# encoder.net
KiCad netlist of a schematic drawn in EAGLE
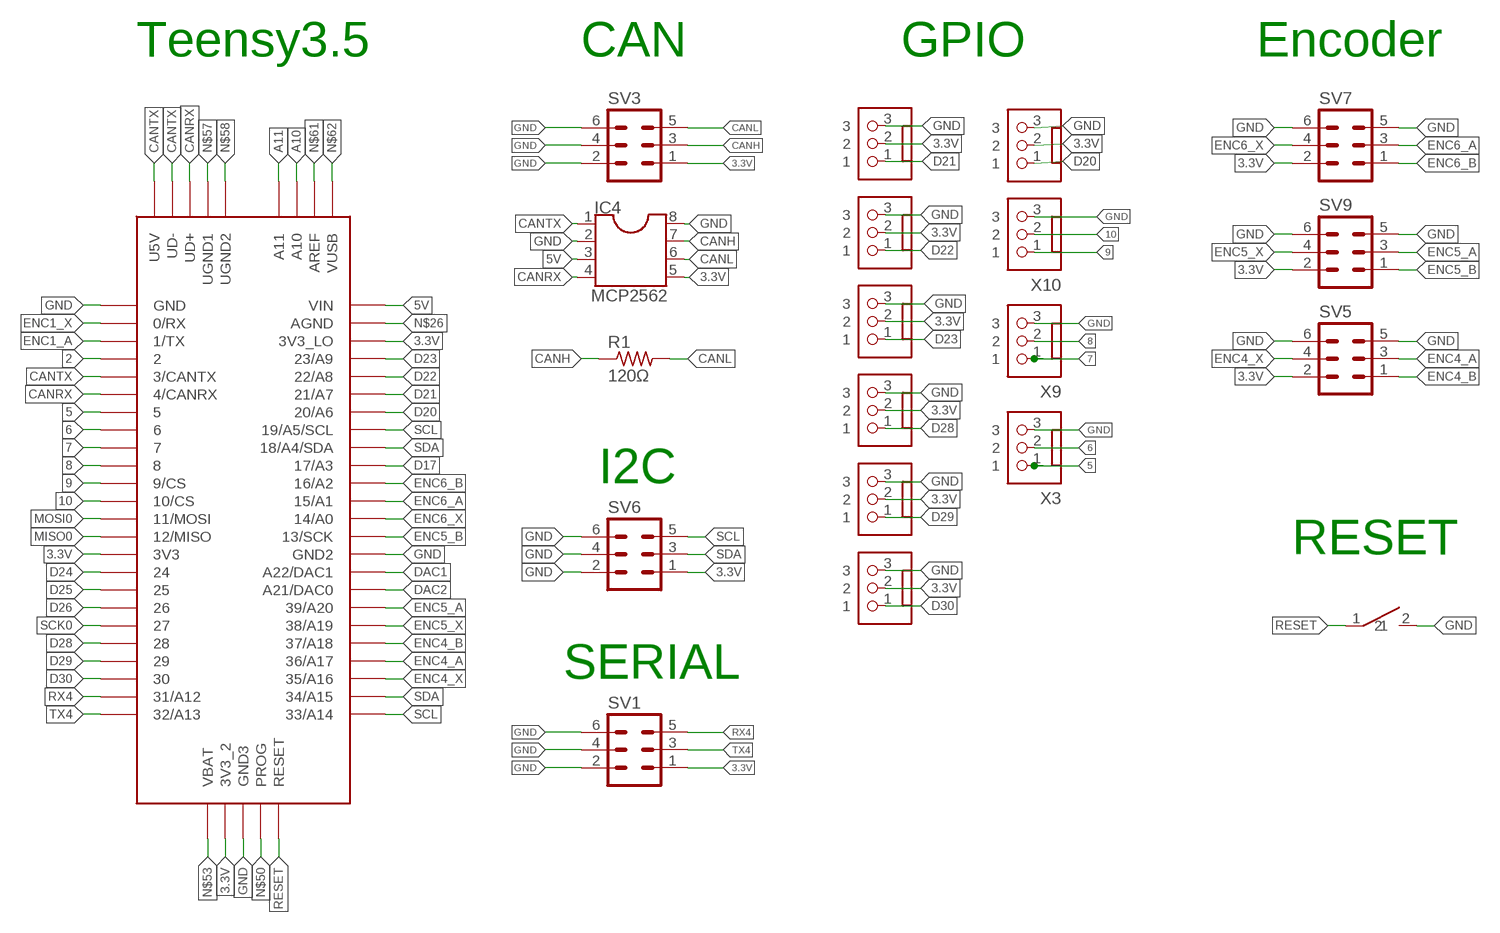
[diagram p0: schematic, sheet 1]

(export (version "E")
  (design (tool "Eeschema 10.0.6"))
  (components
    (comp (ref "IC4")
      (value "MCP2562")
      (footprint "eagle-import:DIL08")
      (libsource (lib "eagle-import") (part "DIL8"))
    )
    (comp (ref "R1")
      (value "120Ω")
      (footprint "eagle-import:0207_7")
      (libsource (lib "eagle-import") (part "R-US_0207/7"))
    )
    (comp (ref "SV1")
      (value "ML6")
      (footprint "eagle-import:ML6")
      (libsource (lib "eagle-import") (part "ML6"))
    )
    (comp (ref "SV3")
      (value "ML6")
      (footprint "eagle-import:ML6")
      (libsource (lib "eagle-import") (part "ML6"))
    )
    (comp (ref "SV5")
      (value "ML6")
      (footprint "eagle-import:ML6")
      (libsource (lib "eagle-import") (part "ML6"))
    )
    (comp (ref "SV6")
      (value "ML6")
      (footprint "eagle-import:ML6")
      (libsource (lib "eagle-import") (part "ML6"))
    )
    (comp (ref "SV7")
      (value "ML6")
      (footprint "eagle-import:ML6")
      (libsource (lib "eagle-import") (part "ML6"))
    )
    (comp (ref "SV9")
      (value "ML6")
      (footprint "eagle-import:ML6")
      (libsource (lib "eagle-import") (part "ML6"))
    )
    (comp (ref "TACT_SWITCH1")
      (value "TACT_SWITCH")
      (footprint "eagle-import:TACT_SWITCH")
      (libsource (lib "eagle-import") (part "TACT_SWITCH"))
    )
    (comp (ref "U$1")
      (value "TEENSY_3.5/3.6")
      (footprint "eagle-import:TEENSY_3.5_3.6")
      (libsource (lib "eagle-import") (part "TEENSY_3.5/3.6"))
    )
    (comp (ref "X3")
      (value "JST-XH-03-PIN-LONG-PAD")
      (footprint "eagle-import:JST-XH-03-PACKAGE-LONG-PAD")
      (libsource (lib "eagle-import") (part "JST-XH-03-PIN-LONG-PAD"))
    )
    (comp (ref "X6")
      (value "JST-XH-03-PIN-LONG-PAD")
      (footprint "eagle-import:JST-XH-03-PACKAGE-LONG-PAD")
      (libsource (lib "eagle-import") (part "JST-XH-03-PIN-LONG-PAD"))
    )
    (comp (ref "X7")
      (value "JST-XH-03-PIN-LONG-PAD")
      (footprint "eagle-import:JST-XH-03-PACKAGE-LONG-PAD")
      (libsource (lib "eagle-import") (part "JST-XH-03-PIN-LONG-PAD"))
    )
    (comp (ref "X8")
      (value "JST-XH-03-PIN-LONG-PAD")
      (footprint "eagle-import:JST-XH-03-PACKAGE-LONG-PAD")
      (libsource (lib "eagle-import") (part "JST-XH-03-PIN-LONG-PAD"))
    )
    (comp (ref "X9")
      (value "JST-XH-03-PIN-LONG-PAD")
      (footprint "eagle-import:JST-XH-03-PACKAGE-LONG-PAD")
      (libsource (lib "eagle-import") (part "JST-XH-03-PIN-LONG-PAD"))
    )
    (comp (ref "X10")
      (value "JST-XH-03-PIN-LONG-PAD")
      (footprint "eagle-import:JST-XH-03-PACKAGE-LONG-PAD")
      (libsource (lib "eagle-import") (part "JST-XH-03-PIN-LONG-PAD"))
    )
    (comp (ref "X12")
      (value "JST-XH-03-PIN-LONG-PAD")
      (footprint "eagle-import:JST-XH-03-PACKAGE-LONG-PAD")
      (libsource (lib "eagle-import") (part "JST-XH-03-PIN-LONG-PAD"))
    )
    (comp (ref "X13")
      (value "JST-XH-03-PIN-LONG-PAD")
      (footprint "eagle-import:JST-XH-03-PACKAGE-LONG-PAD")
      (libsource (lib "eagle-import") (part "JST-XH-03-PIN-LONG-PAD"))
    )
    (comp (ref "X14")
      (value "JST-XH-03-PIN-LONG-PAD")
      (footprint "eagle-import:JST-XH-03-PACKAGE-LONG-PAD")
      (libsource (lib "eagle-import") (part "JST-XH-03-PIN-LONG-PAD"))
    )
    (comp (ref "X15")
      (value "JST-XH-03-PIN-LONG-PAD")
      (footprint "eagle-import:JST-XH-03-PACKAGE-LONG-PAD")
      (libsource (lib "eagle-import") (part "JST-XH-03-PIN-LONG-PAD"))
    )
  )
  (nets
    (net (code "1") (name "2") (class "Default")
      (node (ref "U$1") (pin "2") (pinfunction "2_2") (pintype "bidirectional"))
    )
    (net (code "2") (name "3.3V") (class "Default")
      (node (ref "IC4") (pin "5") (pinfunction "5_5") (pintype "passive"))
      (node (ref "SV1") (pin "1") (pinfunction "1_1") (pintype "passive"))
      (node (ref "SV3") (pin "1") (pinfunction "1_1") (pintype "passive"))
      (node (ref "SV5") (pin "2") (pinfunction "2_2") (pintype "passive"))
      (node (ref "SV6") (pin "1") (pinfunction "1_1") (pintype "passive"))
      (node (ref "SV7") (pin "2") (pinfunction "2_2") (pintype "passive"))
      (node (ref "SV9") (pin "2") (pinfunction "2_2") (pintype "passive"))
      (node (ref "U$1") (pin "3V3") (pinfunction "3V3_3V3") (pintype "bidirectional"))
      (node (ref "U$1") (pin "3V3_2") (pinfunction "3V3_2_3V3_2") (pintype "bidirectional"))
      (node (ref "U$1") (pin "3V3_LO") (pinfunction "3V3_LO_3V3_LO") (pintype "bidirectional"))
      (node (ref "X12") (pin "2") (pinfunction "2_2") (pintype "bidirectional"))
      (node (ref "X13") (pin "2") (pinfunction "2_2") (pintype "bidirectional"))
      (node (ref "X14") (pin "2") (pinfunction "2_2") (pintype "bidirectional"))
      (node (ref "X15") (pin "2") (pinfunction "2_2") (pintype "bidirectional"))
      (node (ref "X6") (pin "2") (pinfunction "2_2") (pintype "bidirectional"))
      (node (ref "X7") (pin "2") (pinfunction "2_2") (pintype "bidirectional"))
      (node (ref "X8") (pin "2") (pinfunction "2_2") (pintype "bidirectional"))
    )
    (net (code "3") (name "5") (class "Default")
      (node (ref "U$1") (pin "5") (pinfunction "5_5") (pintype "bidirectional"))
      (node (ref "X3") (pin "1") (pinfunction "1_1") (pintype "bidirectional"))
    )
    (net (code "4") (name "5V") (class "Default")
      (node (ref "IC4") (pin "3") (pinfunction "3_3") (pintype "passive"))
      (node (ref "U$1") (pin "VIN") (pinfunction "VIN_VIN") (pintype "bidirectional"))
    )
    (net (code "5") (name "6") (class "Default")
      (node (ref "U$1") (pin "6") (pinfunction "6_6") (pintype "bidirectional"))
      (node (ref "X3") (pin "2") (pinfunction "2_2") (pintype "bidirectional"))
    )
    (net (code "6") (name "7") (class "Default")
      (node (ref "U$1") (pin "7") (pinfunction "7_7") (pintype "bidirectional"))
      (node (ref "X9") (pin "1") (pinfunction "1_1") (pintype "bidirectional"))
    )
    (net (code "7") (name "8") (class "Default")
      (node (ref "U$1") (pin "8") (pinfunction "8_8") (pintype "bidirectional"))
      (node (ref "X9") (pin "2") (pinfunction "2_2") (pintype "bidirectional"))
    )
    (net (code "8") (name "9") (class "Default")
      (node (ref "U$1") (pin "9/CS") (pinfunction "9/CS_9/CS") (pintype "bidirectional"))
      (node (ref "X10") (pin "1") (pinfunction "1_1") (pintype "bidirectional"))
    )
    (net (code "9") (name "10") (class "Default")
      (node (ref "U$1") (pin "10/CS") (pinfunction "10/CS_10/CS") (pintype "bidirectional"))
      (node (ref "X10") (pin "2") (pinfunction "2_2") (pintype "bidirectional"))
    )
    (net (code "10") (name "A10") (class "Default")
      (node (ref "U$1") (pin "A10") (pinfunction "A10_A10") (pintype "bidirectional"))
    )
    (net (code "11") (name "A11") (class "Default")
      (node (ref "U$1") (pin "A11") (pinfunction "A11_A11") (pintype "bidirectional"))
    )
    (net (code "12") (name "CANH") (class "Default")
      (node (ref "IC4") (pin "7") (pinfunction "7_7") (pintype "passive"))
      (node (ref "R1") (pin "1") (pinfunction "1_1") (pintype "passive"))
      (node (ref "SV3") (pin "3") (pinfunction "3_3") (pintype "passive"))
    )
    (net (code "13") (name "CANL") (class "Default")
      (node (ref "IC4") (pin "6") (pinfunction "6_6") (pintype "passive"))
      (node (ref "R1") (pin "2") (pinfunction "2_2") (pintype "passive"))
      (node (ref "SV3") (pin "5") (pinfunction "5_5") (pintype "passive"))
    )
    (net (code "14") (name "CANRX") (class "Default")
      (node (ref "IC4") (pin "4") (pinfunction "4_4") (pintype "passive"))
      (node (ref "U$1") (pin "4/CANRX") (pinfunction "4/CANRX_4/CANRX") (pintype "bidirectional"))
      (node (ref "U$1") (pin "UD+") (pinfunction "UD+_UD+") (pintype "bidirectional"))
    )
    (net (code "15") (name "CANTX") (class "Default")
      (node (ref "IC4") (pin "1") (pinfunction "1_1") (pintype "passive"))
      (node (ref "U$1") (pin "3/CANTX") (pinfunction "3/CANTX_3/CANTX") (pintype "bidirectional"))
      (node (ref "U$1") (pin "U5V") (pinfunction "U5V_U5V") (pintype "bidirectional"))
      (node (ref "U$1") (pin "UD-") (pinfunction "UD-_UD-") (pintype "bidirectional"))
    )
    (net (code "16") (name "D17") (class "Default")
      (node (ref "U$1") (pin "17/A3") (pinfunction "17/A3_17/A3") (pintype "bidirectional"))
    )
    (net (code "17") (name "D20") (class "Default")
      (node (ref "U$1") (pin "20/A6") (pinfunction "20/A6_20/A6") (pintype "bidirectional"))
      (node (ref "X6") (pin "1") (pinfunction "1_1") (pintype "bidirectional"))
    )
    (net (code "18") (name "D21") (class "Default")
      (node (ref "U$1") (pin "21/A7") (pinfunction "21/A7_21/A7") (pintype "bidirectional"))
      (node (ref "X7") (pin "1") (pinfunction "1_1") (pintype "bidirectional"))
    )
    (net (code "19") (name "D22") (class "Default")
      (node (ref "U$1") (pin "22/A8") (pinfunction "22/A8_22/A8") (pintype "bidirectional"))
      (node (ref "X12") (pin "1") (pinfunction "1_1") (pintype "bidirectional"))
    )
    (net (code "20") (name "D23") (class "Default")
      (node (ref "U$1") (pin "23/A9") (pinfunction "23/A9_23/A9") (pintype "bidirectional"))
      (node (ref "X13") (pin "1") (pinfunction "1_1") (pintype "bidirectional"))
    )
    (net (code "21") (name "D24") (class "Default")
      (node (ref "U$1") (pin "24") (pinfunction "24_24") (pintype "bidirectional"))
    )
    (net (code "22") (name "D25") (class "Default")
      (node (ref "U$1") (pin "25") (pinfunction "25_25") (pintype "bidirectional"))
    )
    (net (code "23") (name "D26") (class "Default")
      (node (ref "U$1") (pin "26") (pinfunction "26_26") (pintype "bidirectional"))
    )
    (net (code "24") (name "D28") (class "Default")
      (node (ref "U$1") (pin "28") (pinfunction "28_28") (pintype "bidirectional"))
      (node (ref "X8") (pin "1") (pinfunction "1_1") (pintype "bidirectional"))
    )
    (net (code "25") (name "D29") (class "Default")
      (node (ref "U$1") (pin "29") (pinfunction "29_29") (pintype "bidirectional"))
      (node (ref "X14") (pin "1") (pinfunction "1_1") (pintype "bidirectional"))
    )
    (net (code "26") (name "D30") (class "Default")
      (node (ref "U$1") (pin "30") (pinfunction "30_30") (pintype "bidirectional"))
      (node (ref "X15") (pin "1") (pinfunction "1_1") (pintype "bidirectional"))
    )
    (net (code "27") (name "DAC1") (class "Default")
      (node (ref "U$1") (pin "A22/DAC1") (pinfunction "A22/DAC1_A22/DAC1") (pintype "bidirectional"))
    )
    (net (code "28") (name "DAC2") (class "Default")
      (node (ref "U$1") (pin "21/DAC0") (pinfunction "A21/DAC0_21/DAC0") (pintype "bidirectional"))
    )
    (net (code "29") (name "ENC1_A") (class "Default")
      (node (ref "U$1") (pin "1/TX") (pinfunction "1/TX_1/TX") (pintype "bidirectional"))
    )
    (net (code "30") (name "ENC1_X") (class "Default")
      (node (ref "U$1") (pin "0/RX") (pinfunction "0/RX_0/RX") (pintype "bidirectional"))
    )
    (net (code "31") (name "ENC4_A") (class "Default")
      (node (ref "SV5") (pin "3") (pinfunction "3_3") (pintype "passive"))
      (node (ref "U$1") (pin "36/A17") (pinfunction "36/A17_36/A17") (pintype "bidirectional"))
    )
    (net (code "32") (name "ENC4_B") (class "Default")
      (node (ref "SV5") (pin "1") (pinfunction "1_1") (pintype "passive"))
      (node (ref "U$1") (pin "37/A18") (pinfunction "37/A18_37/A18") (pintype "bidirectional"))
    )
    (net (code "33") (name "ENC4_X") (class "Default")
      (node (ref "SV5") (pin "4") (pinfunction "4_4") (pintype "passive"))
      (node (ref "U$1") (pin "35/A16") (pinfunction "35/A16_35/A16") (pintype "bidirectional"))
    )
    (net (code "34") (name "ENC5_A") (class "Default")
      (node (ref "SV9") (pin "3") (pinfunction "3_3") (pintype "passive"))
      (node (ref "U$1") (pin "39/A20") (pinfunction "39/A20_39/A20") (pintype "bidirectional"))
    )
    (net (code "35") (name "ENC5_B") (class "Default")
      (node (ref "SV9") (pin "1") (pinfunction "1_1") (pintype "passive"))
      (node (ref "U$1") (pin "13/SCK") (pinfunction "13/SCK_13/SCK") (pintype "bidirectional"))
    )
    (net (code "36") (name "ENC5_X") (class "Default")
      (node (ref "SV9") (pin "4") (pinfunction "4_4") (pintype "passive"))
      (node (ref "U$1") (pin "38/A19") (pinfunction "38/A19_38/A19") (pintype "bidirectional"))
    )
    (net (code "37") (name "ENC6_A") (class "Default")
      (node (ref "SV7") (pin "3") (pinfunction "3_3") (pintype "passive"))
      (node (ref "U$1") (pin "15/A1") (pinfunction "15/A1_15/A1") (pintype "bidirectional"))
    )
    (net (code "38") (name "ENC6_B") (class "Default")
      (node (ref "SV7") (pin "1") (pinfunction "1_1") (pintype "passive"))
      (node (ref "U$1") (pin "16/A2") (pinfunction "16/A2_16/A2") (pintype "bidirectional"))
    )
    (net (code "39") (name "ENC6_X") (class "Default")
      (node (ref "SV7") (pin "4") (pinfunction "4_4") (pintype "passive"))
      (node (ref "U$1") (pin "14/A0") (pinfunction "14/A0_14/A0") (pintype "bidirectional"))
    )
    (net (code "40") (name "GND") (class "Default")
      (node (ref "IC4") (pin "2") (pinfunction "2_2") (pintype "passive"))
      (node (ref "IC4") (pin "8") (pinfunction "8_8") (pintype "passive"))
      (node (ref "SV1") (pin "2") (pinfunction "2_2") (pintype "passive"))
      (node (ref "SV1") (pin "4") (pinfunction "4_4") (pintype "passive"))
      (node (ref "SV1") (pin "6") (pinfunction "6_6") (pintype "passive"))
      (node (ref "SV3") (pin "2") (pinfunction "2_2") (pintype "passive"))
      (node (ref "SV3") (pin "4") (pinfunction "4_4") (pintype "passive"))
      (node (ref "SV3") (pin "6") (pinfunction "6_6") (pintype "passive"))
      (node (ref "SV5") (pin "5") (pinfunction "5_5") (pintype "passive"))
      (node (ref "SV5") (pin "6") (pinfunction "6_6") (pintype "passive"))
      (node (ref "SV6") (pin "2") (pinfunction "2_2") (pintype "passive"))
      (node (ref "SV6") (pin "4") (pinfunction "4_4") (pintype "passive"))
      (node (ref "SV6") (pin "6") (pinfunction "6_6") (pintype "passive"))
      (node (ref "SV7") (pin "5") (pinfunction "5_5") (pintype "passive"))
      (node (ref "SV7") (pin "6") (pinfunction "6_6") (pintype "passive"))
      (node (ref "SV9") (pin "5") (pinfunction "5_5") (pintype "passive"))
      (node (ref "SV9") (pin "6") (pinfunction "6_6") (pintype "passive"))
      (node (ref "TACT_SWITCH1") (pin "2") (pinfunction "2_2") (pintype "bidirectional"))
      (node (ref "U$1") (pin "GND") (pinfunction "GND_GND") (pintype "bidirectional"))
      (node (ref "U$1") (pin "GND2") (pinfunction "GND2_GND2") (pintype "bidirectional"))
      (node (ref "U$1") (pin "GND3") (pinfunction "GND3_GND3") (pintype "bidirectional"))
      (node (ref "X10") (pin "3") (pinfunction "3_3") (pintype "bidirectional"))
      (node (ref "X12") (pin "3") (pinfunction "3_3") (pintype "bidirectional"))
      (node (ref "X13") (pin "3") (pinfunction "3_3") (pintype "bidirectional"))
      (node (ref "X14") (pin "3") (pinfunction "3_3") (pintype "bidirectional"))
      (node (ref "X15") (pin "3") (pinfunction "3_3") (pintype "bidirectional"))
      (node (ref "X3") (pin "3") (pinfunction "3_3") (pintype "bidirectional"))
      (node (ref "X6") (pin "3") (pinfunction "3_3") (pintype "bidirectional"))
      (node (ref "X7") (pin "3") (pinfunction "3_3") (pintype "bidirectional"))
      (node (ref "X8") (pin "3") (pinfunction "3_3") (pintype "bidirectional"))
      (node (ref "X9") (pin "3") (pinfunction "3_3") (pintype "bidirectional"))
    )
    (net (code "41") (name "MISO0") (class "Default")
      (node (ref "U$1") (pin "12/MISO") (pinfunction "12/MISO_12/MISO") (pintype "bidirectional"))
    )
    (net (code "42") (name "MOSI0") (class "Default")
      (node (ref "U$1") (pin "11/MOSI") (pinfunction "11/MOSI_11/MOSI") (pintype "bidirectional"))
    )
    (net (code "43") (name "N$26") (class "Default")
      (node (ref "U$1") (pin "AGND") (pinfunction "AGND_AGND") (pintype "bidirectional"))
    )
    (net (code "44") (name "N$50") (class "Default")
      (node (ref "U$1") (pin "PROG") (pinfunction "PROG_PROG") (pintype "bidirectional"))
    )
    (net (code "45") (name "N$53") (class "Default")
      (node (ref "U$1") (pin "VBAT") (pinfunction "VBAT_VBAT") (pintype "bidirectional"))
    )
    (net (code "46") (name "N$57") (class "Default")
      (node (ref "U$1") (pin "UGND1") (pinfunction "UGND1_UGND1") (pintype "bidirectional"))
    )
    (net (code "47") (name "N$58") (class "Default")
      (node (ref "U$1") (pin "UGND2") (pinfunction "UGND2_UGND2") (pintype "bidirectional"))
    )
    (net (code "48") (name "N$61") (class "Default")
      (node (ref "U$1") (pin "AREF") (pinfunction "AREF_AREF") (pintype "bidirectional"))
    )
    (net (code "49") (name "N$62") (class "Default")
      (node (ref "U$1") (pin "VUSB") (pinfunction "VUSB_VUSB") (pintype "bidirectional"))
    )
    (net (code "50") (name "RESET") (class "Default")
      (node (ref "TACT_SWITCH1") (pin "1") (pinfunction "1_1") (pintype "bidirectional"))
      (node (ref "U$1") (pin "RESET") (pinfunction "RESET_RESET") (pintype "bidirectional"))
    )
    (net (code "51") (name "RX4") (class "Default")
      (node (ref "SV1") (pin "5") (pinfunction "5_5") (pintype "passive"))
      (node (ref "U$1") (pin "31/A12") (pinfunction "31/A12_31/A12") (pintype "bidirectional"))
    )
    (net (code "52") (name "SCK0") (class "Default")
      (node (ref "U$1") (pin "27") (pinfunction "27_27") (pintype "bidirectional"))
    )
    (net (code "53") (name "SCL") (class "Default")
      (node (ref "SV6") (pin "5") (pinfunction "5_5") (pintype "passive"))
      (node (ref "U$1") (pin "19/A5/SCL") (pinfunction "19/A5/SCL_19/A5/SCL") (pintype "bidirectional"))
      (node (ref "U$1") (pin "33/A14") (pinfunction "33/A14_33/A14") (pintype "bidirectional"))
    )
    (net (code "54") (name "SDA") (class "Default")
      (node (ref "SV6") (pin "3") (pinfunction "3_3") (pintype "passive"))
      (node (ref "U$1") (pin "18/A4/SDA") (pinfunction "18/A4/SDA_18/A4/SDA") (pintype "bidirectional"))
      (node (ref "U$1") (pin "34/A15") (pinfunction "34/A15_34/A15") (pintype "bidirectional"))
    )
    (net (code "55") (name "TX4") (class "Default")
      (node (ref "SV1") (pin "3") (pinfunction "3_3") (pintype "passive"))
      (node (ref "U$1") (pin "32/A13") (pinfunction "32/A13_32/A13") (pintype "bidirectional"))
    )
  )
)
